# I2C-controller-board.net
KiCad netlist of a schematic drawn in EAGLE
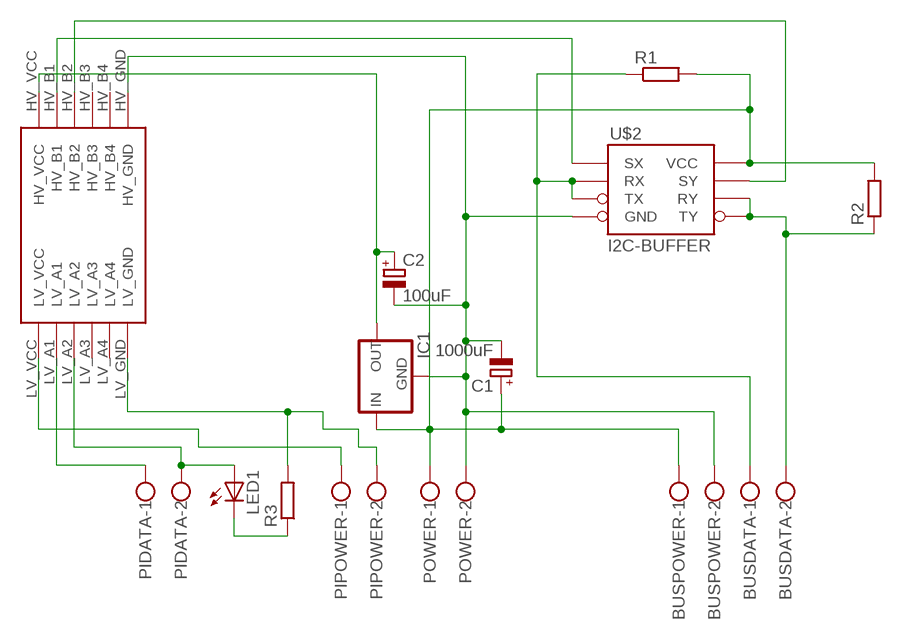
[diagram p0: schematic, sheet 1]

(export (version "E")
  (design (tool "Eeschema 10.0.6"))
  (components
    (comp (ref "BUSDATA")
      (value "W237-102")
      (footprint "eagle-import:W237-102")
      (fields (field (name "MPN") "237-102"))
      (libsource (lib "eagle-import") (part "W237-102"))
    )
    (comp (ref "BUSPOWER")
      (value "W237-102")
      (footprint "eagle-import:W237-102")
      (fields (field (name "MPN") "237-102"))
      (libsource (lib "eagle-import") (part "W237-102"))
    )
    (comp (ref "C1")
      (value "1000uF")
      (footprint "eagle-import:E5-10,5")
      (libsource (lib "eagle-import") (part "CPOL-EUE5-10.5"))
    )
    (comp (ref "C2")
      (value "100uF")
      (footprint "eagle-import:E2,5-6")
      (libsource (lib "eagle-import") (part "CPOL-EUE2.5-6"))
    )
    (comp (ref "IC1")
      (value "78XXL")
      (footprint "eagle-import:78XXL")
      (libsource (lib "eagle-import") (part "78XXL"))
    )
    (comp (ref "LED1")
      (value "LED5MM")
      (footprint "eagle-import:LED5MM")
      (libsource (lib "eagle-import") (part "LED5MM"))
    )
    (comp (ref "PIDATA")
      (value "W237-102")
      (footprint "eagle-import:W237-102")
      (fields (field (name "MPN") "237-102"))
      (libsource (lib "eagle-import") (part "W237-102"))
    )
    (comp (ref "PIPOWER")
      (value "W237-102")
      (footprint "eagle-import:W237-102")
      (fields (field (name "MPN") "237-102"))
      (libsource (lib "eagle-import") (part "W237-102"))
    )
    (comp (ref "POWER")
      (value "W237-102")
      (footprint "eagle-import:W237-102")
      (fields (field (name "MPN") "237-102"))
      (libsource (lib "eagle-import") (part "W237-102"))
    )
    (comp (ref "R1")
      (value "R-EU_0204/7")
      (footprint "eagle-import:0204_7")
      (libsource (lib "eagle-import") (part "R-EU_0204/7"))
    )
    (comp (ref "R2")
      (value "R-EU_0204/7")
      (footprint "eagle-import:0204_7")
      (libsource (lib "eagle-import") (part "R-EU_0204/7"))
    )
    (comp (ref "R3")
      (value "R-EU_0204/7")
      (footprint "eagle-import:0204_7")
      (libsource (lib "eagle-import") (part "R-EU_0204/7"))
    )
    (comp (ref "U$2")
      (value "I2C-BUFFER")
      (footprint "eagle-import:I2C-BUFFER")
      (libsource (lib "eagle-import") (part "I2C-BUFFER"))
    )
    (comp (ref "U$3")
      (value "SPARKFUN_LEVEL_SHIFTER")
      (footprint "eagle-import:SPARKFUN_LEVEL_SHIFTER")
      (libsource (lib "eagle-import") (part "SPARKFUN_LEVEL_SHIFTER"))
    )
  )
  (nets
    (net (code "1") (name "Net-(BUSDATAA-KL)") (class "Default")
      (node (ref "BUSDATA") (pin "1") (pinfunction "KL_1") (pintype "passive"))
      (node (ref "R1") (pin "1") (pinfunction "1_1") (pintype "passive"))
      (node (ref "U$2") (pin "2") (pinfunction "RX_2") (pintype "bidirectional"))
      (node (ref "U$2") (pin "3") (pinfunction "TX_3") (pintype "bidirectional"))
    )
    (net (code "2") (name "Net-(BUSDATAB-KL)") (class "Default")
      (node (ref "BUSDATA") (pin "2") (pinfunction "KL_2") (pintype "passive"))
      (node (ref "R2") (pin "1") (pinfunction "1_1") (pintype "passive"))
      (node (ref "U$2") (pin "5") (pinfunction "TY_5") (pintype "bidirectional"))
      (node (ref "U$2") (pin "6") (pinfunction "RY_6") (pintype "bidirectional"))
    )
    (net (code "3") (name "Net-(BUSPOWERA-KL)") (class "Default")
      (node (ref "BUSPOWER") (pin "1") (pinfunction "KL_1") (pintype "passive"))
      (node (ref "C1") (pin "+") (pinfunction "+_+") (pintype "passive"))
      (node (ref "IC1") (pin "IN") (pinfunction "IN_IN") (pintype "input"))
      (node (ref "POWER") (pin "1") (pinfunction "KL_1") (pintype "passive"))
      (node (ref "R1") (pin "2") (pinfunction "2_2") (pintype "passive"))
      (node (ref "R2") (pin "2") (pinfunction "2_2") (pintype "passive"))
      (node (ref "U$2") (pin "8") (pinfunction "VCC_8") (pintype "bidirectional"))
    )
    (net (code "4") (name "Net-(BUSPOWERB-KL)") (class "Default")
      (node (ref "BUSPOWER") (pin "2") (pinfunction "KL_2") (pintype "passive"))
      (node (ref "C1") (pin "-") (pinfunction "-_-") (pintype "passive"))
      (node (ref "C2") (pin "-") (pinfunction "-_-") (pintype "passive"))
      (node (ref "IC1") (pin "GND") (pinfunction "GND_GND") (pintype "input"))
      (node (ref "POWER") (pin "2") (pinfunction "KL_2") (pintype "passive"))
      (node (ref "U$2") (pin "4") (pinfunction "GND_4") (pintype "bidirectional"))
      (node (ref "U$3") (pin "HV_GND") (pinfunction "HV_GND_HV_GND") (pintype "bidirectional"))
    )
    (net (code "5") (name "Net-(C2-Pad+)") (class "Default")
      (node (ref "C2") (pin "+") (pinfunction "+_+") (pintype "passive"))
      (node (ref "IC1") (pin "OUT") (pinfunction "OUT_OUT") (pintype "passive"))
      (node (ref "U$3") (pin "HV_VCC") (pinfunction "HV_VCC_HV_VCC") (pintype "bidirectional"))
    )
    (net (code "6") (name "Net-(LED1-C)") (class "Default")
      (node (ref "LED1") (pin "K") (pinfunction "C_K") (pintype "passive"))
      (node (ref "R3") (pin "1") (pinfunction "1_1") (pintype "passive"))
    )
    (net (code "7") (name "Net-(PIDATAA-KL)") (class "Default")
      (node (ref "PIDATA") (pin "1") (pinfunction "KL_1") (pintype "passive"))
      (node (ref "U$3") (pin "LV_A1") (pinfunction "LV_A1_LV_A1") (pintype "bidirectional"))
    )
    (net (code "8") (name "Net-(PIDATAB-KL)") (class "Default")
      (node (ref "LED1") (pin "A") (pinfunction "A_A") (pintype "passive"))
      (node (ref "PIDATA") (pin "2") (pinfunction "KL_2") (pintype "passive"))
      (node (ref "U$3") (pin "LV_A2") (pinfunction "LV_A2_LV_A2") (pintype "bidirectional"))
    )
    (net (code "9") (name "Net-(PIPOWERA-KL)") (class "Default")
      (node (ref "PIPOWER") (pin "1") (pinfunction "KL_1") (pintype "passive"))
      (node (ref "U$3") (pin "LV_VCC") (pinfunction "LV_VCC_LV_VCC") (pintype "bidirectional"))
    )
    (net (code "10") (name "Net-(PIPOWERB-KL)") (class "Default")
      (node (ref "PIPOWER") (pin "2") (pinfunction "KL_2") (pintype "passive"))
      (node (ref "R3") (pin "2") (pinfunction "2_2") (pintype "passive"))
      (node (ref "U$3") (pin "LV_GND") (pinfunction "LV_GND_LV_GND") (pintype "bidirectional"))
    )
    (net (code "11") (name "Net-(U$2-SX)") (class "Default")
      (node (ref "U$2") (pin "1") (pinfunction "SX_1") (pintype "bidirectional"))
      (node (ref "U$3") (pin "HV_B1") (pinfunction "HV_B1_HV_B1") (pintype "bidirectional"))
    )
    (net (code "12") (name "Net-(U$2-SY)") (class "Default")
      (node (ref "U$2") (pin "7") (pinfunction "SY_7") (pintype "bidirectional"))
      (node (ref "U$3") (pin "HV_B2") (pinfunction "HV_B2_HV_B2") (pintype "bidirectional"))
    )
    (net (code "13") (name "unconnected-(U$3-PadHV_B3)") (class "Default")
      (node (ref "U$3") (pin "HV_B3") (pinfunction "HV_B3_HV_B3") (pintype "bidirectional"))
    )
    (net (code "14") (name "unconnected-(U$3-PadHV_B4)") (class "Default")
      (node (ref "U$3") (pin "HV_B4") (pinfunction "HV_B4_HV_B4") (pintype "bidirectional"))
    )
    (net (code "15") (name "unconnected-(U$3-PadLV_A3)") (class "Default")
      (node (ref "U$3") (pin "LV_A3") (pinfunction "LV_A3_LV_A3") (pintype "bidirectional"))
    )
    (net (code "16") (name "unconnected-(U$3-PadLV_A4)") (class "Default")
      (node (ref "U$3") (pin "LV_A4") (pinfunction "LV_A4_LV_A4") (pintype "bidirectional"))
    )
  )
)
